# schematic.net
KiCad netlist of a schematic drawn in EasyEDA
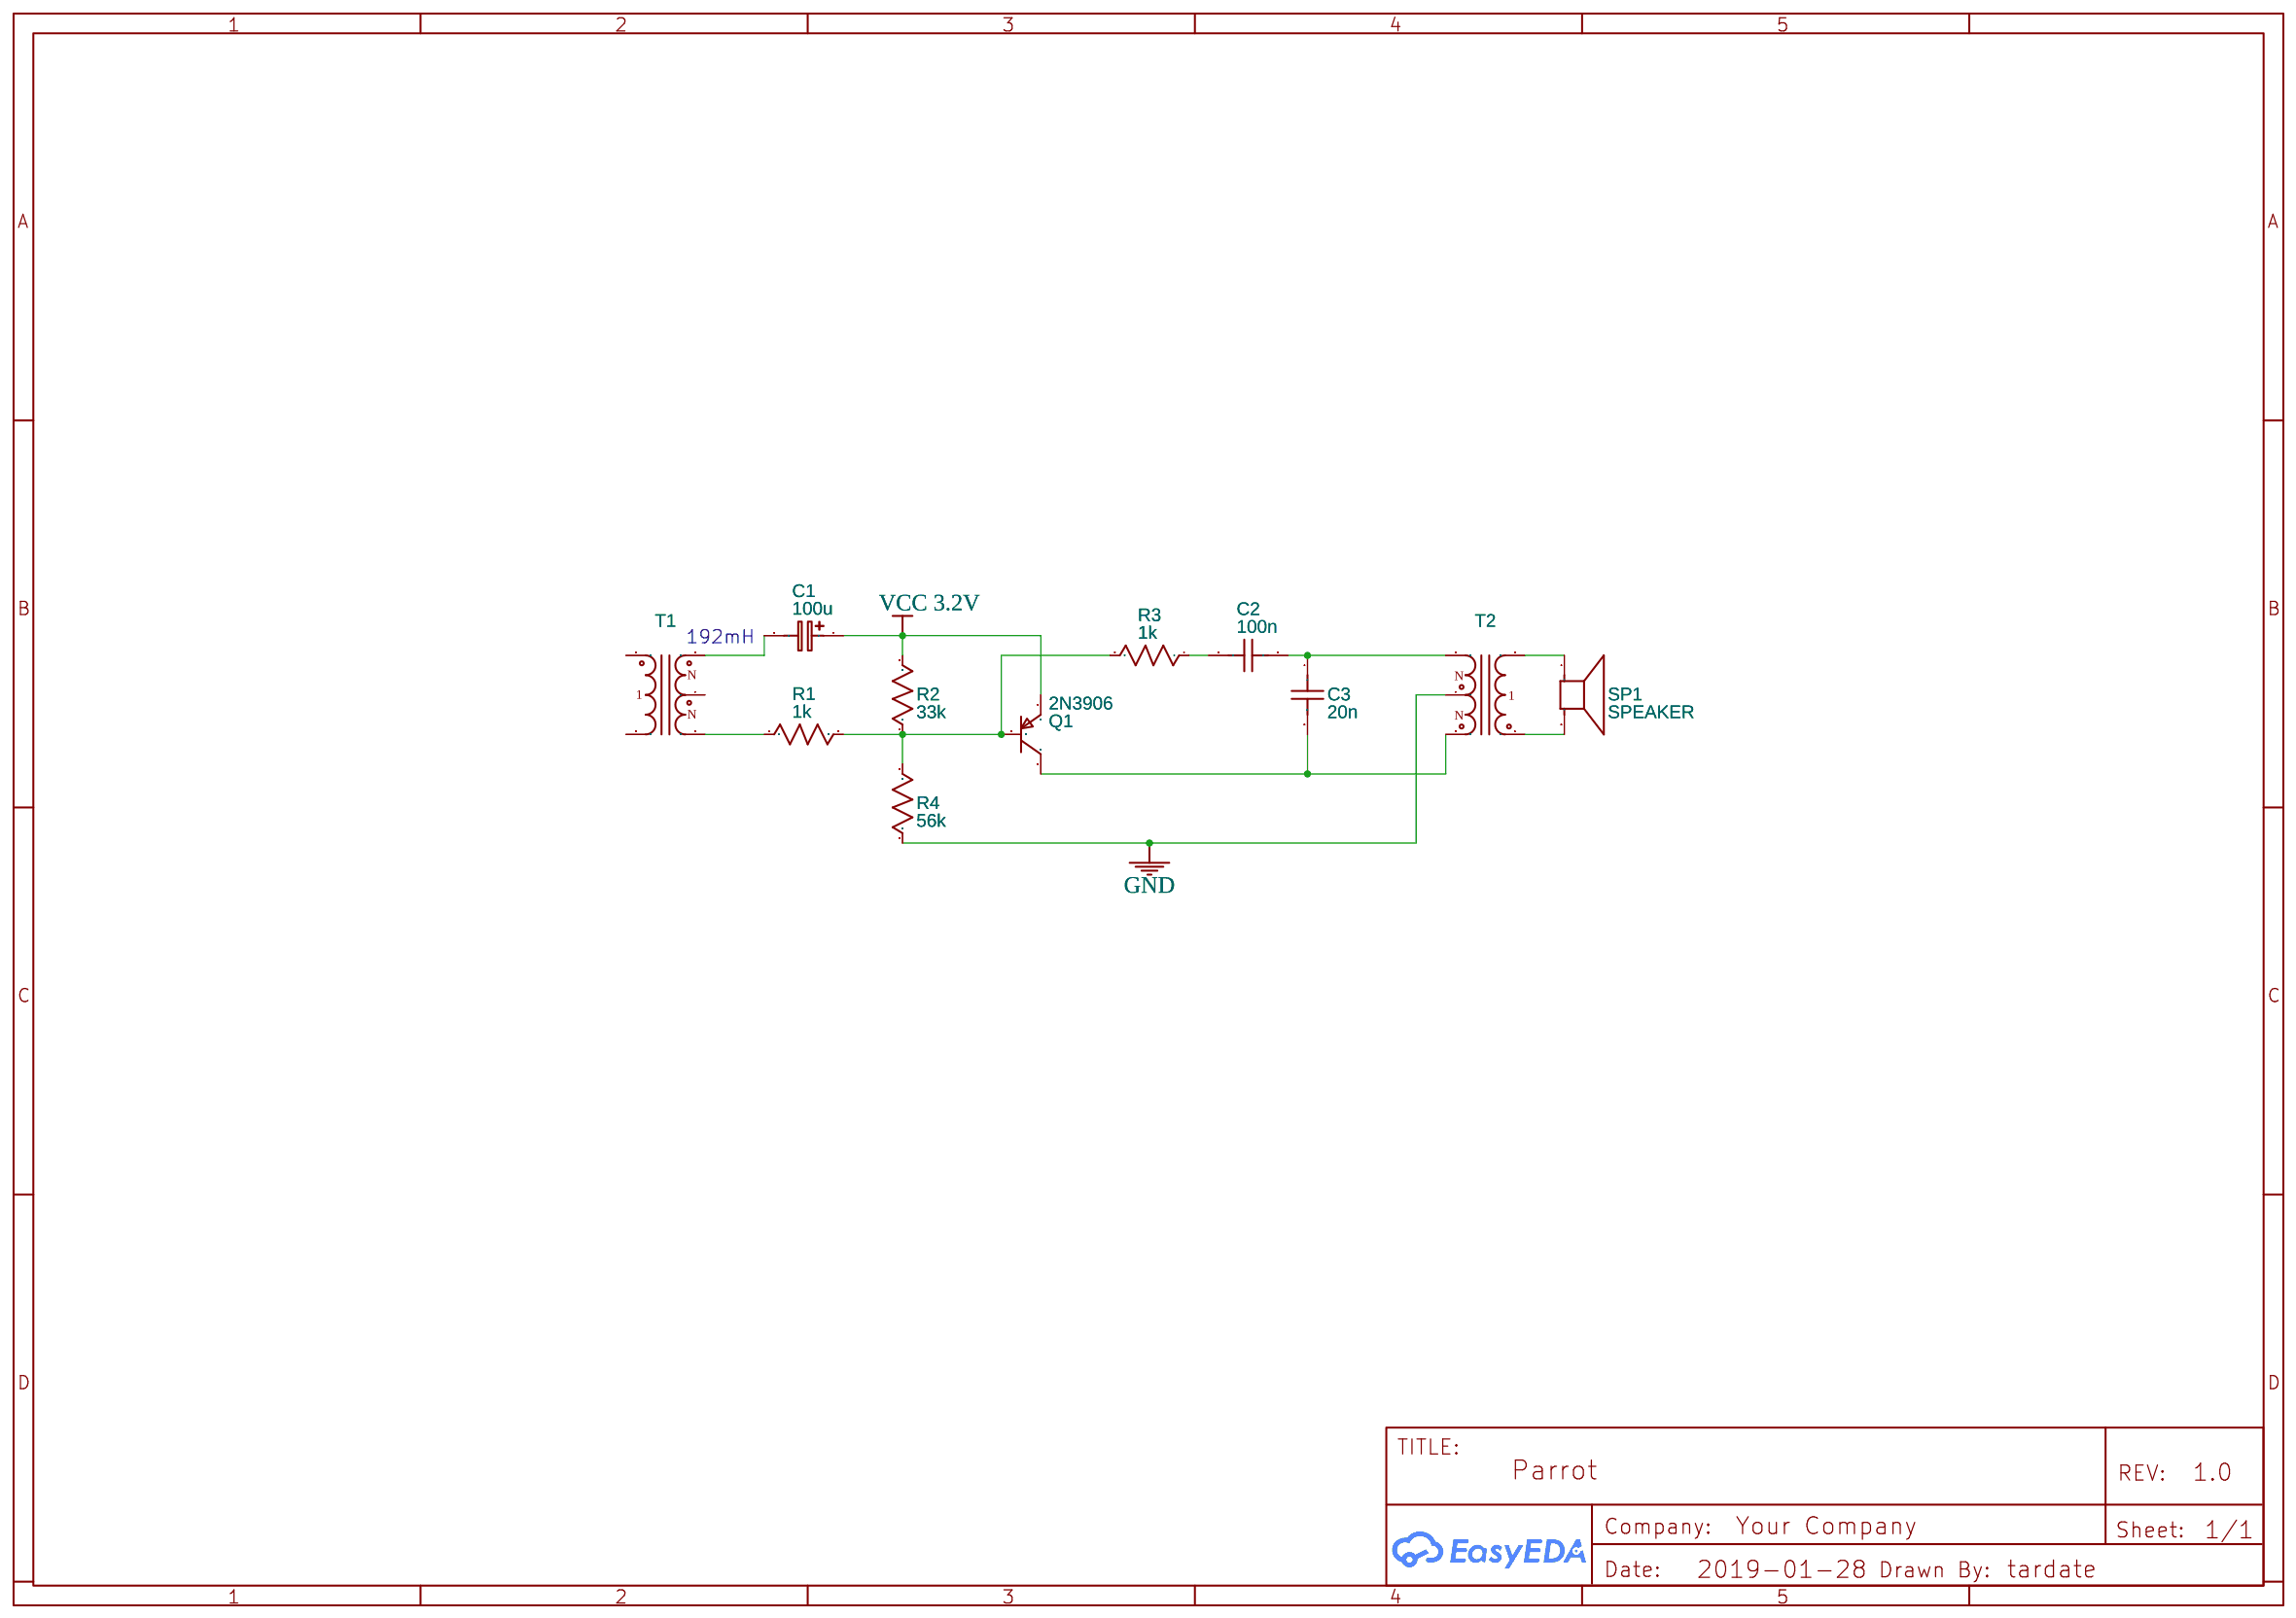
[diagram p0: schematic sheet]

(export (version "E")
  (design (tool "Eeschema 10.0.6"))
  (components
    (comp (ref "C1")
      (value "100u")
      (fields (field (name "BOM_Manufacturer Part") "?"))
      (libsource (lib "") (part "Cap_Electrolytic(TH)_D3.0XF1.5_EU"))
    )
    (comp (ref "C2")
      (value "100n")
      (fields (field (name "BOM_Manufacturer Part") "?"))
      (libsource (lib "") (part "Cap_RAD-0.1_US_1"))
    )
    (comp (ref "C3")
      (value "20n")
      (fields (field (name "BOM_Manufacturer Part") "?"))
      (libsource (lib "") (part "Cap_RAD-0.1_US"))
    )
    (comp (ref "Q1")
      (value "2N3906")
      (fields (field (name "BOM_Supplier Part") "C9809"))
      (libsource (lib "") (part "Unknown_510_365"))
    )
    (comp (ref "R1")
      (value "1k")
      (fields (field (name "BOM_Manufacturer Part") "?"))
      (libsource (lib "") (part "Res_AXIAL-0.3(1/8W)_US_1"))
    )
    (comp (ref "R2")
      (value "33k")
      (fields (field (name "BOM_Manufacturer Part") "?"))
      (libsource (lib "") (part "Res_AXIAL-0.3(1/8W)_US"))
    )
    (comp (ref "R3")
      (value "1k")
      (fields (field (name "BOM_Manufacturer Part") "?"))
      (libsource (lib "") (part "Res_AXIAL-0.3(1/8W)_US_2"))
    )
    (comp (ref "R4")
      (value "56k")
      (fields (field (name "BOM_Manufacturer Part") "?"))
      (libsource (lib "") (part "Res_AXIAL-0.3(1/8W)_US"))
    )
    (comp (ref "SP1")
      (value "SPEAKER")
      (fields (field (name "BOM_Manufacturer Part") "?"))
      (libsource (lib "") (part "Unknown_795_345"))
    )
    (comp (ref "T1")
      (value "TRANSFORMER_CENTRE_TAPPED_US")
      (fields (field (name "BOM_Manufacturer Part") "?"))
      (libsource (lib "") (part "Unknown_330_345"))
    )
    (comp (ref "T2")
      (value "TRANSFORMER_CENTRE_TAPPED_US")
      (fields (field (name "BOM_Manufacturer Part") "?"))
      (libsource (lib "") (part "Unknown_745_345"))
    )
  )
  (nets
    (net (code "1") (name "GND") (class "Default")
      (node (ref "R4") (pin "1") (pinfunction "1_1") (pintype "unspecified"))
      (node (ref "T2") (pin "4") (pinfunction "4_4") (pintype "unspecified"))
    )
    (net (code "2") (name "Net-(C1-Pad2)") (class "Default")
      (node (ref "C1") (pin "2") (pinfunction "2_2") (pintype "unspecified"))
      (node (ref "T1") (pin "5") (pinfunction "5_5") (pintype "unspecified"))
    )
    (net (code "3") (name "Net-(C2-Pad1)") (class "Default")
      (node (ref "C2") (pin "1") (pinfunction "1_1") (pintype "unspecified"))
      (node (ref "C3") (pin "1") (pinfunction "1_1") (pintype "unspecified"))
      (node (ref "T2") (pin "3") (pinfunction "3_3") (pintype "unspecified"))
    )
    (net (code "4") (name "Net-(C2-Pad2)") (class "Default")
      (node (ref "C2") (pin "2") (pinfunction "2_2") (pintype "unspecified"))
      (node (ref "R3") (pin "1") (pinfunction "1_1") (pintype "unspecified"))
    )
    (net (code "5") (name "Net-(Q1-B)") (class "Default")
      (node (ref "Q1") (pin "2") (pinfunction "B_2") (pintype "unspecified"))
      (node (ref "R1") (pin "2") (pinfunction "2_2") (pintype "unspecified"))
      (node (ref "R2") (pin "1") (pinfunction "1_1") (pintype "unspecified"))
      (node (ref "R3") (pin "2") (pinfunction "2_2") (pintype "unspecified"))
      (node (ref "R4") (pin "2") (pinfunction "2_2") (pintype "unspecified"))
    )
    (net (code "6") (name "Net-(Q1-C)") (class "Default")
      (node (ref "C3") (pin "2") (pinfunction "2_2") (pintype "unspecified"))
      (node (ref "Q1") (pin "3") (pinfunction "C_3") (pintype "unspecified"))
      (node (ref "T2") (pin "5") (pinfunction "5_5") (pintype "unspecified"))
    )
    (net (code "7") (name "Net-(R1-Pad1)") (class "Default")
      (node (ref "R1") (pin "1") (pinfunction "1_1") (pintype "unspecified"))
      (node (ref "T1") (pin "3") (pinfunction "3_3") (pintype "unspecified"))
    )
    (net (code "8") (name "Net-(SP1-+)") (class "Default")
      (node (ref "SP1") (pin "1") (pinfunction "+_1") (pintype "unspecified"))
      (node (ref "T2") (pin "2") (pinfunction "2_2") (pintype "unspecified"))
    )
    (net (code "9") (name "Net-(SP1--)") (class "Default")
      (node (ref "SP1") (pin "2") (pinfunction "-_2") (pintype "unspecified"))
      (node (ref "T2") (pin "1") (pinfunction "1_1") (pintype "unspecified"))
    )
    (net (code "10") (name "VCC 3.2V") (class "Default")
      (node (ref "C1") (pin "1") (pinfunction "1_1") (pintype "unspecified"))
      (node (ref "Q1") (pin "1") (pinfunction "E_1") (pintype "unspecified"))
      (node (ref "R2") (pin "2") (pinfunction "2_2") (pintype "unspecified"))
    )
    (net (code "11") (name "unconnected-(T1-Pad1)") (class "Default")
      (node (ref "T1") (pin "1") (pinfunction "1_1") (pintype "unspecified"))
    )
    (net (code "12") (name "unconnected-(T1-Pad2)") (class "Default")
      (node (ref "T1") (pin "2") (pinfunction "2_2") (pintype "unspecified"))
    )
    (net (code "13") (name "unconnected-(T1-Pad4)") (class "Default")
      (node (ref "T1") (pin "4") (pinfunction "4_4") (pintype "unspecified"))
    )
  )
)
